# I2C_GPIO_Expansion.net
KiCad netlist of a schematic drawn in Altium Designer
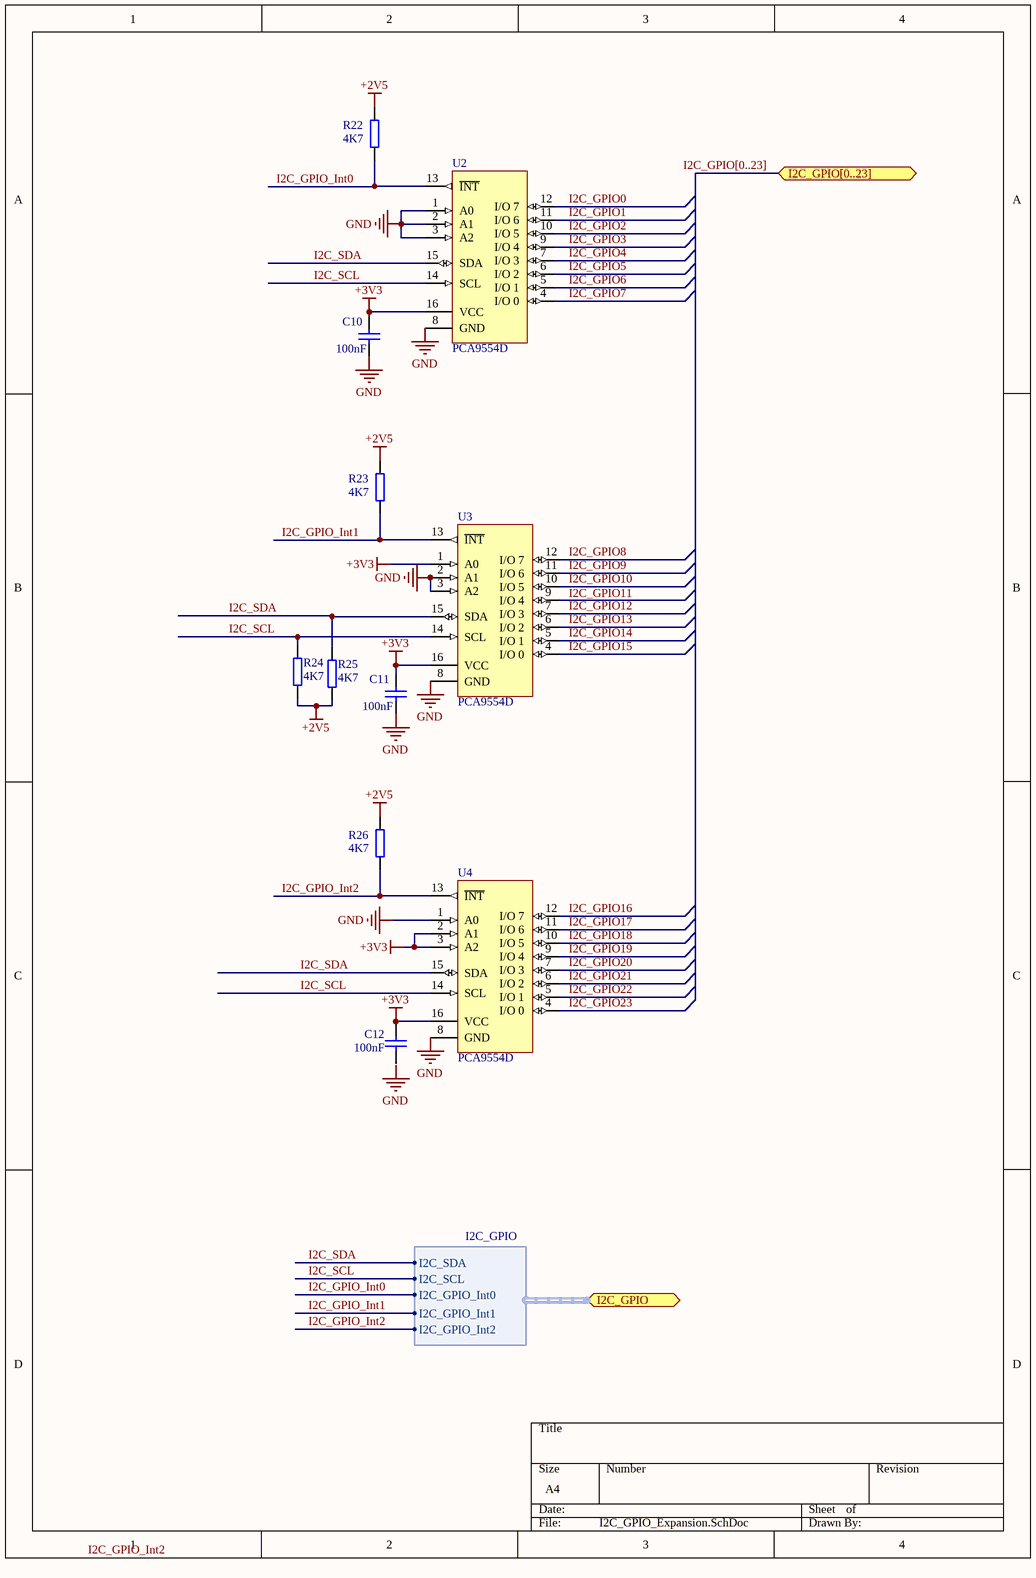
[diagram p0: I2C_GPIO_Expansion.SchDoc]

(export (version "E")
  (design (tool "Eeschema 10.0.6"))
  (components
    (comp (ref "C10")
      (value "100nF")
      (footprint "CC1608-0603")
      (description "Capacitor")
      (fields
        (field (name "TOLERANCE") "±10%")
        (field (name "VOLTAGE") "16V")
        (field (name "PUBLISHER") "Altium Limited")
      )
      (libsource (lib "wr_switch") (part "Cap"))
    )
    (comp (ref "C11")
      (value "100nF")
      (footprint "CC1608-0603")
      (description "Capacitor")
      (fields
        (field (name "TOLERANCE") "±10%")
        (field (name "VOLTAGE") "16V")
        (field (name "PUBLISHER") "Altium Limited")
      )
      (libsource (lib "wr_switch") (part "Cap"))
    )
    (comp (ref "C12")
      (value "100nF")
      (footprint "CC1608-0603")
      (description "Capacitor")
      (fields
        (field (name "TOLERANCE") "±10%")
        (field (name "VOLTAGE") "16V")
        (field (name "PUBLISHER") "Altium Limited")
      )
      (libsource (lib "wr_switch") (part "Cap"))
    )
    (comp (ref "R22")
      (value "4K7")
      (footprint "0603")
      (description "SMD Resistor")
      (fields (field (name "TOLERANCE") "±1%"))
      (libsource (lib "wr_switch") (part "RES_SMD"))
    )
    (comp (ref "R23")
      (value "4K7")
      (footprint "0603")
      (description "SMD Resistor")
      (fields (field (name "TOLERANCE") "±1%"))
      (libsource (lib "wr_switch") (part "RES_SMD"))
    )
    (comp (ref "R24")
      (value "4K7")
      (footprint "0603")
      (description "SMD Resistor")
      (fields (field (name "TOLERANCE") "±1%"))
      (libsource (lib "wr_switch") (part "RES_SMD"))
    )
    (comp (ref "R25")
      (value "4K7")
      (footprint "0603")
      (description "SMD Resistor")
      (fields (field (name "TOLERANCE") "±1%"))
      (libsource (lib "wr_switch") (part "RES_SMD"))
    )
    (comp (ref "R26")
      (value "4K7")
      (footprint "0603")
      (description "SMD Resistor")
      (fields (field (name "TOLERANCE") "±1%"))
      (libsource (lib "wr_switch") (part "RES_SMD"))
    )
    (comp (ref "U2")
      (value "PCA9554D")
      (footprint "SOP65P640X110-20N")
      (description "8-bit I2C-bus SMBus I/O port with interrupt")
      (libsource (lib "wr_switch") (part "PCA9554D"))
    )
    (comp (ref "U3")
      (value "PCA9554D")
      (footprint "SOP65P640X110-20N")
      (description "8-bit I2C-bus SMBus I/O port with interrupt")
      (libsource (lib "wr_switch") (part "PCA9554D"))
    )
    (comp (ref "U4")
      (value "PCA9554D")
      (footprint "SOP65P640X110-20N")
      (description "8-bit I2C-bus SMBus I/O port with interrupt")
      (libsource (lib "wr_switch") (part "PCA9554D"))
    )
  )
  (nets
    (net (code "2") (name "+2V5") (class "Default")
      (node (ref "R22") (pin "2") (pinfunction "2_2") (pintype "passive"))
      (node (ref "R23") (pin "2") (pinfunction "2_2") (pintype "passive"))
      (node (ref "R24") (pin "1") (pinfunction "1_1") (pintype "passive"))
      (node (ref "R25") (pin "1") (pinfunction "1_1") (pintype "passive"))
      (node (ref "R26") (pin "2") (pinfunction "2_2") (pintype "passive"))
    )
    (net (code "3") (name "+3V3") (class "Default")
      (node (ref "C10") (pin "2") (pinfunction "2_2") (pintype "passive"))
      (node (ref "C11") (pin "2") (pinfunction "2_2") (pintype "passive"))
      (node (ref "C12") (pin "1") (pinfunction "1_1") (pintype "passive"))
      (node (ref "U2") (pin "16") (pinfunction "VCC_16") (pintype "power_in"))
      (node (ref "U3") (pin "1") (pinfunction "A0_1") (pintype "input"))
      (node (ref "U3") (pin "16") (pinfunction "VCC_16") (pintype "power_in"))
      (node (ref "U4") (pin "16") (pinfunction "VCC_16") (pintype "power_in"))
      (node (ref "U4") (pin "2") (pinfunction "A1_2") (pintype "input"))
      (node (ref "U4") (pin "3") (pinfunction "A2_3") (pintype "input"))
    )
    (net (code "4") (name "/I2C_GPIO0") (class "Default")
      (node (ref "U2") (pin "12") (pinfunction "I/O_7_12") (pintype "bidirectional"))
    )
    (net (code "5") (name "/I2C_GPIO1") (class "Default")
      (node (ref "U2") (pin "11") (pinfunction "I/O_6_11") (pintype "bidirectional"))
    )
    (net (code "6") (name "/I2C_GPIO2") (class "Default")
      (node (ref "U2") (pin "10") (pinfunction "I/O_5_10") (pintype "bidirectional"))
    )
    (net (code "7") (name "/I2C_GPIO3") (class "Default")
      (node (ref "U2") (pin "9") (pinfunction "I/O_4_9") (pintype "bidirectional"))
    )
    (net (code "8") (name "/I2C_GPIO4") (class "Default")
      (node (ref "U2") (pin "7") (pinfunction "I/O_3_7") (pintype "bidirectional"))
    )
    (net (code "9") (name "/I2C_GPIO5") (class "Default")
      (node (ref "U2") (pin "6") (pinfunction "I/O_2_6") (pintype "bidirectional"))
    )
    (net (code "10") (name "/I2C_GPIO6") (class "Default")
      (node (ref "U2") (pin "5") (pinfunction "I/O_1_5") (pintype "bidirectional"))
    )
    (net (code "11") (name "/I2C_GPIO7") (class "Default")
      (node (ref "U2") (pin "4") (pinfunction "I/O_0_4") (pintype "bidirectional"))
    )
    (net (code "12") (name "/I2C_GPIO8") (class "Default")
      (node (ref "U3") (pin "12") (pinfunction "I/O_7_12") (pintype "bidirectional"))
    )
    (net (code "13") (name "/I2C_GPIO9") (class "Default")
      (node (ref "U3") (pin "11") (pinfunction "I/O_6_11") (pintype "bidirectional"))
    )
    (net (code "14") (name "/I2C_GPIO10") (class "Default")
      (node (ref "U3") (pin "10") (pinfunction "I/O_5_10") (pintype "bidirectional"))
    )
    (net (code "16") (name "/I2C_GPIO12") (class "Default")
      (node (ref "U3") (pin "7") (pinfunction "I/O_3_7") (pintype "bidirectional"))
    )
    (net (code "17") (name "/I2C_GPIO13") (class "Default")
      (node (ref "U3") (pin "6") (pinfunction "I/O_2_6") (pintype "bidirectional"))
    )
    (net (code "18") (name "/I2C_GPIO14") (class "Default")
      (node (ref "U3") (pin "5") (pinfunction "I/O_1_5") (pintype "bidirectional"))
    )
    (net (code "19") (name "/I2C_GPIO15") (class "Default")
      (node (ref "U3") (pin "4") (pinfunction "I/O_0_4") (pintype "bidirectional"))
    )
    (net (code "20") (name "/I2C_GPIO16") (class "Default")
      (node (ref "U4") (pin "12") (pinfunction "I/O_7_12") (pintype "bidirectional"))
    )
    (net (code "21") (name "/I2C_GPIO17") (class "Default")
      (node (ref "U4") (pin "11") (pinfunction "I/O_6_11") (pintype "bidirectional"))
    )
    (net (code "22") (name "/I2C_GPIO18") (class "Default")
      (node (ref "U4") (pin "10") (pinfunction "I/O_5_10") (pintype "bidirectional"))
    )
    (net (code "23") (name "/I2C_GPIO19") (class "Default")
      (node (ref "U4") (pin "9") (pinfunction "I/O_4_9") (pintype "bidirectional"))
    )
    (net (code "24") (name "/I2C_GPIO20") (class "Default")
      (node (ref "U4") (pin "7") (pinfunction "I/O_3_7") (pintype "bidirectional"))
    )
    (net (code "25") (name "/I2C_GPIO21") (class "Default")
      (node (ref "U4") (pin "6") (pinfunction "I/O_2_6") (pintype "bidirectional"))
    )
    (net (code "26") (name "/I2C_GPIO22") (class "Default")
      (node (ref "U4") (pin "5") (pinfunction "I/O_1_5") (pintype "bidirectional"))
    )
    (net (code "27") (name "/I2C_GPIO23") (class "Default")
      (node (ref "U4") (pin "4") (pinfunction "I/O_0_4") (pintype "bidirectional"))
    )
    (net (code "29") (name "/I2C_GPIO_Int0") (class "Default")
      (node (ref "R22") (pin "1") (pinfunction "1_1") (pintype "passive"))
      (node (ref "U2") (pin "13") (pinfunction "~{INT}_13") (pintype "output"))
    )
    (net (code "30") (name "/I2C_GPIO_Int1") (class "Default")
      (node (ref "R23") (pin "1") (pinfunction "1_1") (pintype "passive"))
      (node (ref "U3") (pin "13") (pinfunction "~{INT}_13") (pintype "output"))
    )
    (net (code "31") (name "/I2C_GPIO_Int2") (class "Default")
      (node (ref "R26") (pin "1") (pinfunction "1_1") (pintype "passive"))
      (node (ref "U4") (pin "13") (pinfunction "~{INT}_13") (pintype "output"))
    )
    (net (code "32") (name "/I2C_SCL") (class "Default")
      (node (ref "R24") (pin "2") (pinfunction "2_2") (pintype "passive"))
      (node (ref "U2") (pin "14") (pinfunction "SCL_14") (pintype "input"))
      (node (ref "U3") (pin "14") (pinfunction "SCL_14") (pintype "input"))
      (node (ref "U4") (pin "14") (pinfunction "SCL_14") (pintype "input"))
    )
    (net (code "33") (name "/I2C_SDA") (class "Default")
      (node (ref "R25") (pin "2") (pinfunction "2_2") (pintype "passive"))
      (node (ref "U2") (pin "15") (pinfunction "SDA_15") (pintype "bidirectional"))
      (node (ref "U3") (pin "15") (pinfunction "SDA_15") (pintype "bidirectional"))
      (node (ref "U4") (pin "15") (pinfunction "SDA_15") (pintype "bidirectional"))
    )
    (net (code "35") (name "GND") (class "Default")
      (node (ref "C10") (pin "1") (pinfunction "1_1") (pintype "passive"))
      (node (ref "C11") (pin "1") (pinfunction "1_1") (pintype "passive"))
      (node (ref "U2") (pin "1") (pinfunction "A0_1") (pintype "input"))
      (node (ref "U2") (pin "2") (pinfunction "A1_2") (pintype "input"))
      (node (ref "U2") (pin "3") (pinfunction "A2_3") (pintype "input"))
      (node (ref "U2") (pin "8") (pinfunction "GND_8") (pintype "power_in"))
      (node (ref "U3") (pin "2") (pinfunction "A1_2") (pintype "input"))
      (node (ref "U3") (pin "3") (pinfunction "A2_3") (pintype "input"))
      (node (ref "U3") (pin "8") (pinfunction "GND_8") (pintype "power_in"))
      (node (ref "U4") (pin "1") (pinfunction "A0_1") (pintype "input"))
      (node (ref "U4") (pin "8") (pinfunction "GND_8") (pintype "power_in"))
    )
    (net (code "36") (name "unconnected-(C12-Pad2)") (class "Default")
      (node (ref "C12") (pin "2") (pinfunction "2_2") (pintype "passive"))
    )
    (net (code "37") (name "unconnected-(U3-I{slash}O_4-Pad9)") (class "Default")
      (node (ref "U3") (pin "9") (pinfunction "I/O_4_9") (pintype "bidirectional"))
    )
  )
)
